# Adafruit_tftcaptouchshield_v2_3.net
KiCad netlist of a schematic drawn in EAGLE
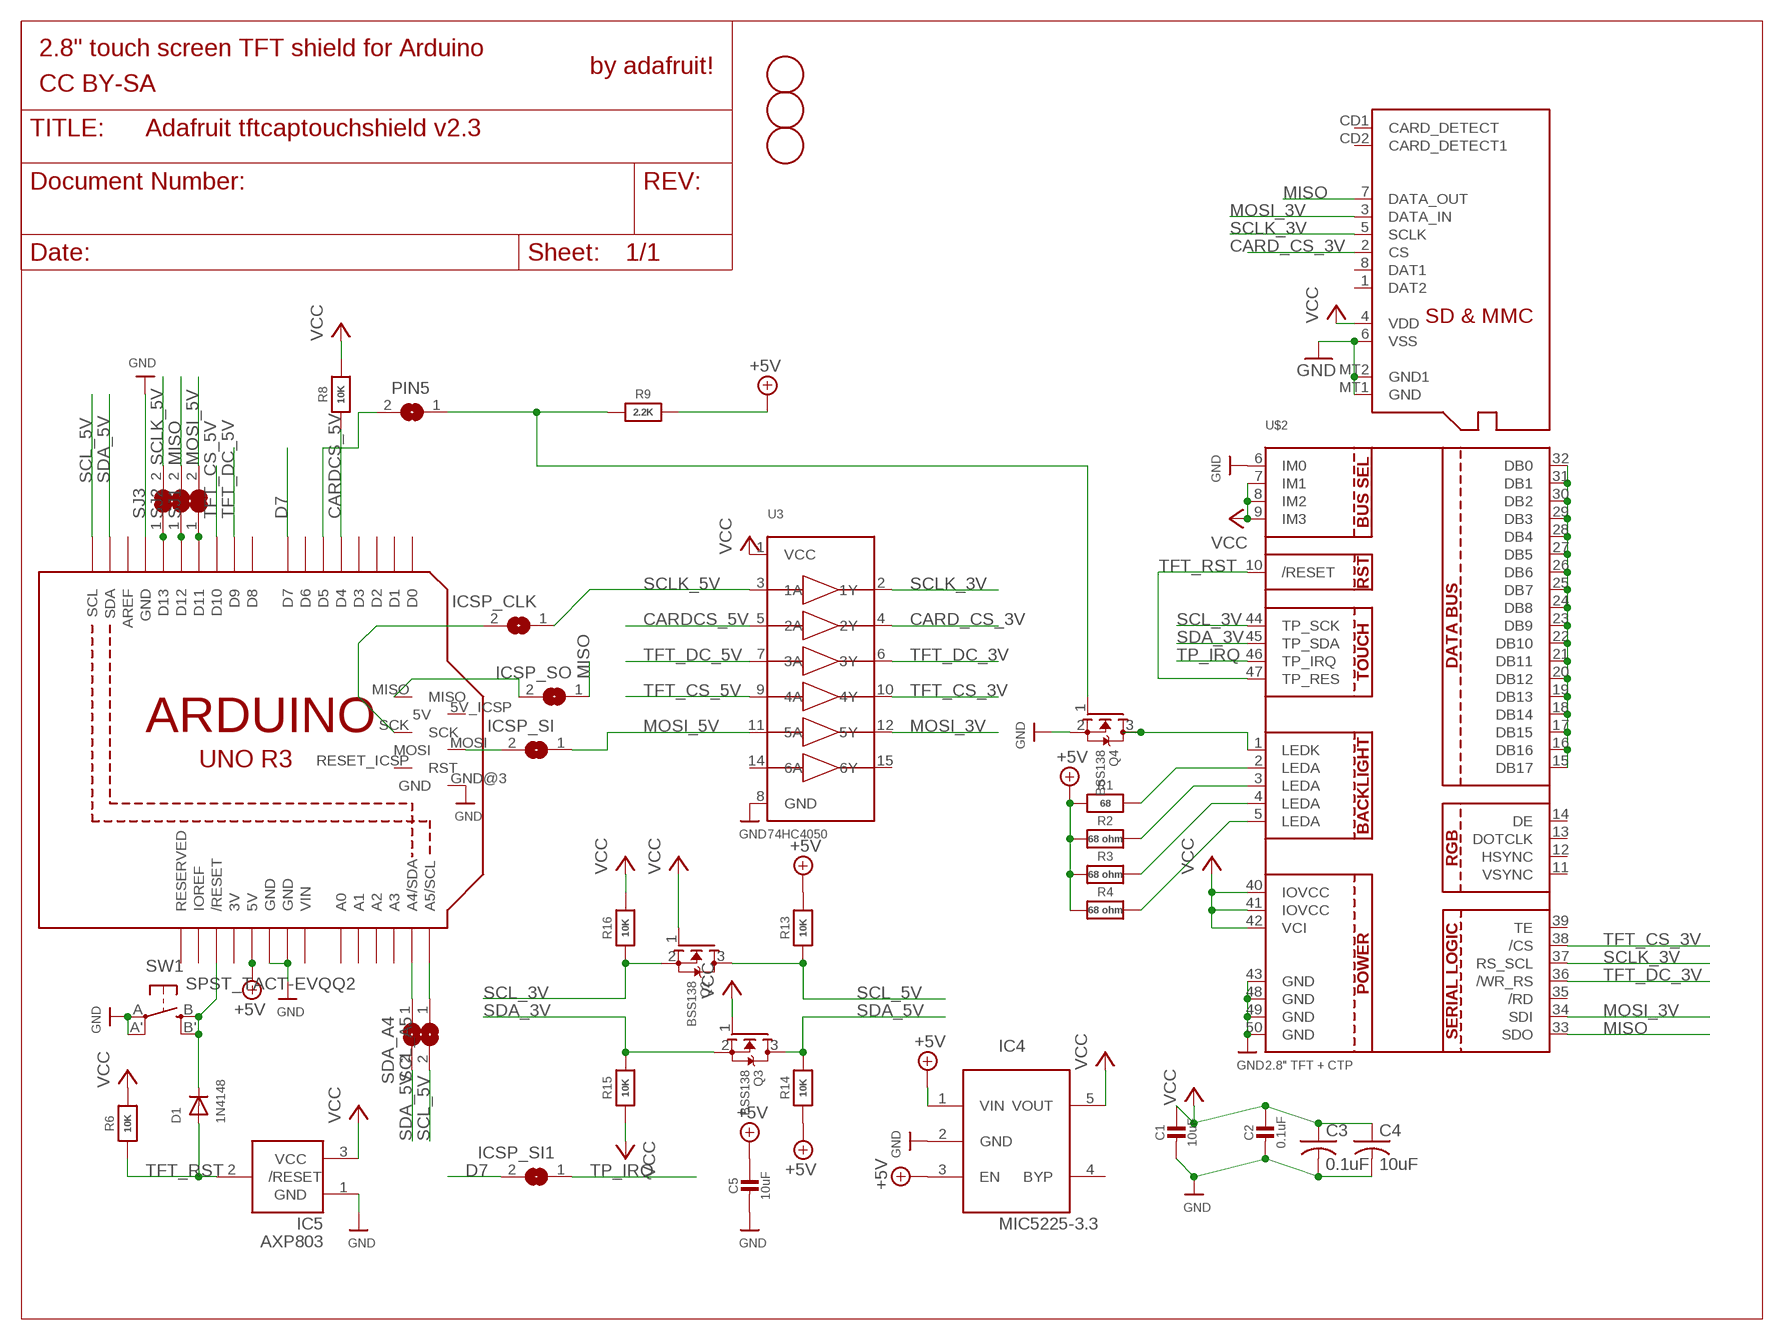
[diagram p0: schematic, sheet 1]

(export (version "E")
  (design (tool "Eeschema 10.0.6"))
  (components
    (comp (ref "C1")
      (value "10uF")
      (footprint "eagle-import:0805-NO")
      (libsource (lib "eagle-import") (part "CAP_CERAMIC0805-NOOUTLINE"))
    )
    (comp (ref "C2")
      (value "0.1uF")
      (footprint "eagle-import:0805-NO")
      (libsource (lib "eagle-import") (part "CAP_CERAMIC0805-NOOUTLINE"))
    )
    (comp (ref "C3")
      (value "0.1uF")
      (footprint "eagle-import:C0805K")
      (libsource (lib "eagle-import") (part "C-USC0805K"))
    )
    (comp (ref "C4")
      (value "10uF")
      (footprint "eagle-import:C0805K")
      (libsource (lib "eagle-import") (part "C-USC0805K"))
    )
    (comp (ref "C5")
      (value "10uF")
      (footprint "eagle-import:0805-NO")
      (libsource (lib "eagle-import") (part "CAP_CERAMIC0805-NOOUTLINE"))
    )
    (comp (ref "D1")
      (value "1N4148")
      (footprint "eagle-import:SOD-323F")
      (libsource (lib "eagle-import") (part "DIODESOD-323F"))
    )
    (comp (ref "IC4")
      (value "MIC5225-3.3")
      (footprint "eagle-import:SOT23-5L")
      (libsource (lib "eagle-import") (part "LP298XS"))
    )
    (comp (ref "IC5")
      (value "AXP803")
      (footprint "eagle-import:SOT23")
      (libsource (lib "eagle-import") (part "AXP083-SAG"))
    )
    (comp (ref "ICSP_CLK")
      (value "SOLDERJUMPERREFLOW_NOPASTE")
      (footprint "eagle-import:SOLDERJUMPER_REFLOW_NOPASTE")
      (libsource (lib "eagle-import") (part "SOLDERJUMPERREFLOW_NOPASTE"))
    )
    (comp (ref "ICSP_SI")
      (value "SOLDERJUMPERREFLOW_NOPASTE")
      (footprint "eagle-import:SOLDERJUMPER_REFLOW_NOPASTE")
      (libsource (lib "eagle-import") (part "SOLDERJUMPERREFLOW_NOPASTE"))
    )
    (comp (ref "ICSP_SI1")
      (value "SOLDERJUMPERREFLOW_NOPASTE")
      (footprint "eagle-import:SOLDERJUMPER_REFLOW_NOPASTE")
      (libsource (lib "eagle-import") (part "SOLDERJUMPERREFLOW_NOPASTE"))
    )
    (comp (ref "ICSP_SO")
      (value "SOLDERJUMPERREFLOW_NOPASTE")
      (footprint "eagle-import:SOLDERJUMPER_REFLOW_NOPASTE")
      (libsource (lib "eagle-import") (part "SOLDERJUMPERREFLOW_NOPASTE"))
    )
    (comp (ref "PIN5")
      (value "SOLDERJUMPERREFLOW_NOPASTE")
      (footprint "eagle-import:SOLDERJUMPER_REFLOW_NOPASTE")
      (libsource (lib "eagle-import") (part "SOLDERJUMPERREFLOW_NOPASTE"))
    )
    (comp (ref "Q2")
      (value "BSS138")
      (footprint "eagle-import:SOT23-WIDE")
      (libsource (lib "eagle-import") (part "MOSFET-NWIDE"))
    )
    (comp (ref "Q3")
      (value "BSS138")
      (footprint "eagle-import:SOT23-WIDE")
      (libsource (lib "eagle-import") (part "MOSFET-NWIDE"))
    )
    (comp (ref "Q4")
      (value "BSS138")
      (footprint "eagle-import:SOT23-WIDE")
      (libsource (lib "eagle-import") (part "MOSFET-NWIDE"))
    )
    (comp (ref "R1")
      (value "68")
      (footprint "eagle-import:0805-NO")
      (libsource (lib "eagle-import") (part "RESISTOR0805_NOOUTLINE"))
    )
    (comp (ref "R2")
      (value "68 ohm")
      (footprint "eagle-import:0805-NO")
      (libsource (lib "eagle-import") (part "RESISTOR0805_NOOUTLINE"))
    )
    (comp (ref "R3")
      (value "68 ohm")
      (footprint "eagle-import:0805-NO")
      (libsource (lib "eagle-import") (part "RESISTOR0805_NOOUTLINE"))
    )
    (comp (ref "R4")
      (value "68 ohm")
      (footprint "eagle-import:0805-NO")
      (libsource (lib "eagle-import") (part "RESISTOR0805_NOOUTLINE"))
    )
    (comp (ref "R6")
      (value "10K")
      (footprint "eagle-import:0805-NO")
      (libsource (lib "eagle-import") (part "RESISTOR0805_NOOUTLINE"))
    )
    (comp (ref "R8")
      (value "10K")
      (footprint "eagle-import:0805-NO")
      (libsource (lib "eagle-import") (part "RESISTOR0805_NOOUTLINE"))
    )
    (comp (ref "R9")
      (value "2.2K")
      (footprint "eagle-import:0805-NO")
      (libsource (lib "eagle-import") (part "RESISTOR0805_NOOUTLINE"))
    )
    (comp (ref "R13")
      (value "10K")
      (footprint "eagle-import:0805-NO")
      (libsource (lib "eagle-import") (part "RESISTOR0805_NOOUTLINE"))
    )
    (comp (ref "R14")
      (value "10K")
      (footprint "eagle-import:0805-NO")
      (libsource (lib "eagle-import") (part "RESISTOR0805_NOOUTLINE"))
    )
    (comp (ref "R15")
      (value "10K")
      (footprint "eagle-import:0805-NO")
      (libsource (lib "eagle-import") (part "RESISTOR0805_NOOUTLINE"))
    )
    (comp (ref "R16")
      (value "10K")
      (footprint "eagle-import:0805-NO")
      (libsource (lib "eagle-import") (part "RESISTOR0805_NOOUTLINE"))
    )
    (comp (ref "SCL_A5")
      (value "SOLDERJUMPERREFLOW_NOPASTE")
      (footprint "eagle-import:SOLDERJUMPER_REFLOW_NOPASTE")
      (libsource (lib "eagle-import") (part "SOLDERJUMPERREFLOW_NOPASTE"))
    )
    (comp (ref "SDA_A4")
      (value "SOLDERJUMPERREFLOW_NOPASTE")
      (footprint "eagle-import:SOLDERJUMPER_REFLOW_NOPASTE")
      (libsource (lib "eagle-import") (part "SOLDERJUMPERREFLOW_NOPASTE"))
    )
    (comp (ref "SJ1")
      (value "SOLDERJUMPER_CLOSED")
      (footprint "eagle-import:SOLDERJUMPER_CLOSEDWIRE")
      (libsource (lib "eagle-import") (part "SOLDERJUMPER_CLOSED"))
    )
    (comp (ref "SJ2")
      (value "SOLDERJUMPER_CLOSED")
      (footprint "eagle-import:SOLDERJUMPER_CLOSEDWIRE")
      (libsource (lib "eagle-import") (part "SOLDERJUMPER_CLOSED"))
    )
    (comp (ref "SJ3")
      (value "SOLDERJUMPER_CLOSED")
      (footprint "eagle-import:SOLDERJUMPER_CLOSEDWIRE")
      (libsource (lib "eagle-import") (part "SOLDERJUMPER_CLOSED"))
    )
    (comp (ref "SW1")
      (value "SPST_TACT-EVQQ2")
      (footprint "eagle-import:EVQ-Q2")
      (libsource (lib "eagle-import") (part "SPST_TACT-EVQQ2"))
    )
    (comp (ref "U$2")
      (value "2.8\" TFT + CTP")
      (footprint "eagle-import:TFT_2.83IN_240X320_50PIN")
      (libsource (lib "eagle-import") (part "DISP_LCD_CTP28_SAMPLE"))
    )
    (comp (ref "U$3")
      (value "MICROSD")
      (footprint "eagle-import:MICROSD")
      (libsource (lib "eagle-import") (part "MICROSD"))
    )
    (comp (ref "U$10")
      (value "FIDUCIAL")
      (footprint "eagle-import:FIDUCIAL_1MM")
      (libsource (lib "eagle-import") (part "FIDUCIAL"))
    )
    (comp (ref "U$11")
      (value "FIDUCIAL")
      (footprint "eagle-import:FIDUCIAL_1MM")
      (libsource (lib "eagle-import") (part "FIDUCIAL"))
    )
    (comp (ref "U$17")
      (value "ARDUINO_R3_ICSPSMT")
      (footprint "eagle-import:ARDUINOR3_ICSP_SMT")
      (libsource (lib "eagle-import") (part "ARDUINO_R3_ICSPSMT"))
    )
    (comp (ref "U$19")
      (value "FIDUCIAL")
      (footprint "eagle-import:FIDUCIAL_1MM")
      (libsource (lib "eagle-import") (part "FIDUCIAL"))
    )
    (comp (ref "U3")
      (value "74HC4050")
      (footprint "eagle-import:SOIC16")
      (libsource (lib "eagle-import") (part "74HC4050D"))
    )
  )
  (nets
    (net (code "1") (name "+5V") (class "Default")
      (node (ref "C5") (pin "1") (pinfunction "1_1") (pintype "passive"))
      (node (ref "IC4") (pin "1") (pinfunction "VIN_1") (pintype "bidirectional"))
      (node (ref "IC4") (pin "3") (pinfunction "EN_3") (pintype "bidirectional"))
      (node (ref "R1") (pin "1") (pinfunction "1_1") (pintype "passive"))
      (node (ref "R13") (pin "2") (pinfunction "2_2") (pintype "passive"))
      (node (ref "R14") (pin "1") (pinfunction "1_1") (pintype "passive"))
      (node (ref "R2") (pin "1") (pinfunction "1_1") (pintype "passive"))
      (node (ref "R3") (pin "1") (pinfunction "1_1") (pintype "passive"))
      (node (ref "R4") (pin "1") (pinfunction "1_1") (pintype "passive"))
      (node (ref "R9") (pin "2") (pinfunction "2_2") (pintype "passive"))
      (node (ref "U$17") (pin "5V") (pinfunction "5V_5V") (pintype "power_in"))
    )
    (net (code "2") (name "/3V") (class "Default")
      (node (ref "U$17") (pin "3V") (pinfunction "3V_3V") (pintype "power_in"))
    )
    (net (code "3") (name "/CARDCS_5V") (class "Default")
      (node (ref "R8") (pin "1") (pinfunction "1_1") (pintype "passive"))
      (node (ref "U$17") (pin "D4") (pinfunction "D4_D4") (pintype "bidirectional"))
      (node (ref "U3") (pin "5") (pinfunction "2A_5") (pintype "bidirectional"))
    )
    (net (code "4") (name "/CARD_CS_3V") (class "Default")
      (node (ref "U$3") (pin "2") (pinfunction "CS_2") (pintype "input"))
      (node (ref "U3") (pin "4") (pinfunction "2Y_4") (pintype "bidirectional"))
    )
    (net (code "5") (name "/D7") (class "Default")
      (node (ref "ICSP_SI1") (pin "2") (pinfunction "2_2") (pintype "passive"))
      (node (ref "U$17") (pin "D7") (pinfunction "D7_D7") (pintype "bidirectional"))
    )
    (net (code "6") (name "/MISO") (class "Default")
      (node (ref "ICSP_SO") (pin "1") (pinfunction "1_1") (pintype "passive"))
      (node (ref "SJ2") (pin "2") (pinfunction "2_2") (pintype "passive"))
      (node (ref "U$2") (pin "33") (pinfunction "SDO_33") (pintype "bidirectional"))
      (node (ref "U$3") (pin "7") (pinfunction "DATA_OUT_7") (pintype "output"))
    )
    (net (code "7") (name "/MOSI_3V") (class "Default")
      (node (ref "U$2") (pin "34") (pinfunction "SDI_34") (pintype "bidirectional"))
      (node (ref "U$3") (pin "3") (pinfunction "DATA_IN_3") (pintype "input"))
      (node (ref "U3") (pin "12") (pinfunction "5Y_12") (pintype "bidirectional"))
    )
    (net (code "8") (name "/MOSI_5V") (class "Default")
      (node (ref "ICSP_SI") (pin "1") (pinfunction "1_1") (pintype "passive"))
      (node (ref "SJ1") (pin "2") (pinfunction "2_2") (pintype "passive"))
      (node (ref "U3") (pin "11") (pinfunction "5A_11") (pintype "bidirectional"))
    )
    (net (code "9") (name "/SCLK_3V") (class "Default")
      (node (ref "U$2") (pin "37") (pinfunction "RS_SCL_37") (pintype "bidirectional"))
      (node (ref "U$3") (pin "5") (pinfunction "SCLK_5") (pintype "input"))
      (node (ref "U3") (pin "2") (pinfunction "1Y_2") (pintype "bidirectional"))
    )
    (net (code "10") (name "/SCLK_5V") (class "Default")
      (node (ref "ICSP_CLK") (pin "1") (pinfunction "1_1") (pintype "passive"))
      (node (ref "SJ3") (pin "2") (pinfunction "2_2") (pintype "passive"))
      (node (ref "U3") (pin "3") (pinfunction "1A_3") (pintype "bidirectional"))
    )
    (net (code "11") (name "/SCL_3V") (class "Default")
      (node (ref "Q2") (pin "2") (pinfunction "S_2") (pintype "bidirectional"))
      (node (ref "R16") (pin "1") (pinfunction "1_1") (pintype "passive"))
      (node (ref "U$2") (pin "44") (pinfunction "TP_SCK_44") (pintype "bidirectional"))
    )
    (net (code "12") (name "/SCL_5V") (class "Default")
      (node (ref "Q2") (pin "3") (pinfunction "D_3") (pintype "bidirectional"))
      (node (ref "R13") (pin "1") (pinfunction "1_1") (pintype "passive"))
      (node (ref "SCL_A5") (pin "2") (pinfunction "2_2") (pintype "passive"))
      (node (ref "U$17") (pin "SCL") (pinfunction "SCL_SCL") (pintype "bidirectional"))
    )
    (net (code "13") (name "/SDA_3V") (class "Default")
      (node (ref "Q3") (pin "2") (pinfunction "S_2") (pintype "bidirectional"))
      (node (ref "R15") (pin "2") (pinfunction "2_2") (pintype "passive"))
      (node (ref "U$2") (pin "45") (pinfunction "TP_SDA_45") (pintype "bidirectional"))
    )
    (net (code "14") (name "/SDA_5V") (class "Default")
      (node (ref "Q3") (pin "3") (pinfunction "D_3") (pintype "bidirectional"))
      (node (ref "R14") (pin "2") (pinfunction "2_2") (pintype "passive"))
      (node (ref "SDA_A4") (pin "2") (pinfunction "2_2") (pintype "passive"))
      (node (ref "U$17") (pin "SDA") (pinfunction "SDA_SDA") (pintype "bidirectional"))
    )
    (net (code "15") (name "/TFT_CS_3V") (class "Default")
      (node (ref "U$2") (pin "38") (pinfunction "/CS_38") (pintype "bidirectional"))
      (node (ref "U3") (pin "10") (pinfunction "4Y_10") (pintype "bidirectional"))
    )
    (net (code "16") (name "/TFT_CS_5V") (class "Default")
      (node (ref "U$17") (pin "D10") (pinfunction "D10_D10") (pintype "bidirectional"))
      (node (ref "U3") (pin "9") (pinfunction "4A_9") (pintype "bidirectional"))
    )
    (net (code "17") (name "/TFT_DC_3V") (class "Default")
      (node (ref "U$2") (pin "36") (pinfunction "/WR_RS_36") (pintype "bidirectional"))
      (node (ref "U3") (pin "6") (pinfunction "3Y_6") (pintype "bidirectional"))
    )
    (net (code "18") (name "/TFT_DC_5V") (class "Default")
      (node (ref "U$17") (pin "D9") (pinfunction "D9_D9") (pintype "bidirectional"))
      (node (ref "U3") (pin "7") (pinfunction "3A_7") (pintype "bidirectional"))
    )
    (net (code "19") (name "/TFT_RST") (class "Default")
      (node (ref "D1") (pin "A") (pinfunction "A_A") (pintype "passive"))
      (node (ref "IC5") (pin "2") (pinfunction "/RESET_2") (pintype "output"))
      (node (ref "R6") (pin "1") (pinfunction "1_1") (pintype "passive"))
      (node (ref "U$2") (pin "10") (pinfunction "/RESET_10") (pintype "bidirectional"))
      (node (ref "U$2") (pin "47") (pinfunction "TP_RES_47") (pintype "bidirectional"))
    )
    (net (code "20") (name "/TP_IRQ") (class "Default")
      (node (ref "ICSP_SI1") (pin "1") (pinfunction "1_1") (pintype "passive"))
      (node (ref "U$2") (pin "46") (pinfunction "TP_IRQ_46") (pintype "bidirectional"))
    )
    (net (code "21") (name "/VIN") (class "Default")
      (node (ref "U$17") (pin "VIN") (pinfunction "VIN_VIN") (pintype "power_in"))
    )
    (net (code "22") (name "GND") (class "Default")
      (node (ref "C1") (pin "2") (pinfunction "2_2") (pintype "passive"))
      (node (ref "C2") (pin "2") (pinfunction "2_2") (pintype "passive"))
      (node (ref "C3") (pin "2") (pinfunction "2_2") (pintype "passive"))
      (node (ref "C4") (pin "2") (pinfunction "2_2") (pintype "passive"))
      (node (ref "C5") (pin "2") (pinfunction "2_2") (pintype "passive"))
      (node (ref "IC4") (pin "2") (pinfunction "GND_2") (pintype "bidirectional"))
      (node (ref "IC5") (pin "1") (pinfunction "GND_1") (pintype "power_in"))
      (node (ref "Q4") (pin "2") (pinfunction "S_2") (pintype "bidirectional"))
      (node (ref "SW1") (pin "A") (pinfunction "P_A") (pintype "passive"))
      (node (ref "SW1") (pin "A'") (pinfunction "P1_A'") (pintype "passive"))
      (node (ref "U$17") (pin "GND") (pinfunction "GND_GND") (pintype "power_in"))
      (node (ref "U$17") (pin "GND@1") (pinfunction "GND_GND@1") (pintype "power_in"))
      (node (ref "U$17") (pin "GND@2") (pinfunction "GND_GND@2") (pintype "power_in"))
      (node (ref "U$17") (pin "GND@3") (pinfunction "GND_GND@3") (pintype "passive"))
      (node (ref "U$2") (pin "43") (pinfunction "GND_43") (pintype "bidirectional"))
      (node (ref "U$2") (pin "48") (pinfunction "GND_48") (pintype "bidirectional"))
      (node (ref "U$2") (pin "49") (pinfunction "GND_49") (pintype "bidirectional"))
      (node (ref "U$2") (pin "50") (pinfunction "GND_50") (pintype "bidirectional"))
      (node (ref "U$2") (pin "6") (pinfunction "IM0_6") (pintype "bidirectional"))
      (node (ref "U$3") (pin "6") (pinfunction "VSS_6") (pintype "power_in"))
      (node (ref "U$3") (pin "MT1") (pinfunction "GND_MT1") (pintype "power_in"))
      (node (ref "U$3") (pin "MT2") (pinfunction "GND1_MT2") (pintype "power_in"))
      (node (ref "U3") (pin "8") (pinfunction "GND_8") (pintype "bidirectional"))
    )
    (net (code "23") (name "Net-(ICSP_CLK-Pad2)") (class "Default")
      (node (ref "ICSP_CLK") (pin "2") (pinfunction "2_2") (pintype "passive"))
      (node (ref "U$17") (pin "SCK") (pinfunction "SCK_SCK") (pintype "passive"))
    )
    (net (code "24") (name "Net-(ICSP_SI-Pad2)") (class "Default")
      (node (ref "ICSP_SI") (pin "2") (pinfunction "2_2") (pintype "passive"))
      (node (ref "U$17") (pin "MOSI") (pinfunction "MOSI_MOSI") (pintype "passive"))
    )
    (net (code "25") (name "Net-(ICSP_SO-Pad2)") (class "Default")
      (node (ref "ICSP_SO") (pin "2") (pinfunction "2_2") (pintype "passive"))
      (node (ref "U$17") (pin "MISO") (pinfunction "MISO_MISO") (pintype "passive"))
    )
    (net (code "26") (name "Net-(PIN5-Pad2)") (class "Default")
      (node (ref "PIN5") (pin "2") (pinfunction "2_2") (pintype "passive"))
      (node (ref "U$17") (pin "D5") (pinfunction "D5_D5") (pintype "bidirectional"))
    )
    (net (code "27") (name "Net-(Q4-D)") (class "Default")
      (node (ref "Q4") (pin "3") (pinfunction "D_3") (pintype "bidirectional"))
      (node (ref "U$2") (pin "1") (pinfunction "LEDK_1") (pintype "bidirectional"))
    )
    (net (code "28") (name "Net-(Q4-G)") (class "Default")
      (node (ref "PIN5") (pin "1") (pinfunction "1_1") (pintype "passive"))
      (node (ref "Q4") (pin "1") (pinfunction "G_1") (pintype "bidirectional"))
      (node (ref "R9") (pin "1") (pinfunction "1_1") (pintype "passive"))
    )
    (net (code "29") (name "Net-(R1-Pad2)") (class "Default")
      (node (ref "R1") (pin "2") (pinfunction "2_2") (pintype "passive"))
      (node (ref "U$2") (pin "2") (pinfunction "LEDA_2") (pintype "bidirectional"))
    )
    (net (code "30") (name "Net-(R2-Pad2)") (class "Default")
      (node (ref "R2") (pin "2") (pinfunction "2_2") (pintype "passive"))
      (node (ref "U$2") (pin "3") (pinfunction "LEDA_3") (pintype "bidirectional"))
    )
    (net (code "31") (name "Net-(R3-Pad2)") (class "Default")
      (node (ref "R3") (pin "2") (pinfunction "2_2") (pintype "passive"))
      (node (ref "U$2") (pin "4") (pinfunction "LEDA_4") (pintype "bidirectional"))
    )
    (net (code "32") (name "Net-(R4-Pad2)") (class "Default")
      (node (ref "R4") (pin "2") (pinfunction "2_2") (pintype "passive"))
      (node (ref "U$2") (pin "5") (pinfunction "LEDA_5") (pintype "bidirectional"))
    )
    (net (code "33") (name "Net-(SJ1-Pad1)") (class "Default")
      (node (ref "SJ1") (pin "1") (pinfunction "1_1") (pintype "passive"))
      (node (ref "U$17") (pin "D11") (pinfunction "D11_D11") (pintype "bidirectional"))
    )
    (net (code "34") (name "Net-(SJ2-Pad1)") (class "Default")
      (node (ref "SJ2") (pin "1") (pinfunction "1_1") (pintype "passive"))
      (node (ref "U$17") (pin "D12") (pinfunction "D12_D12") (pintype "bidirectional"))
    )
    (net (code "35") (name "Net-(SJ3-Pad1)") (class "Default")
      (node (ref "SJ3") (pin "1") (pinfunction "1_1") (pintype "passive"))
      (node (ref "U$17") (pin "D13") (pinfunction "D13_D13") (pintype "bidirectional"))
    )
    (net (code "36") (name "Net-(SW1-S)") (class "Default")
      (node (ref "D1") (pin "C") (pinfunction "C_C") (pintype "passive"))
      (node (ref "SW1") (pin "B") (pinfunction "S_B") (pintype "passive"))
      (node (ref "SW1") (pin "B'") (pinfunction "S1_B'") (pintype "passive"))
      (node (ref "U$17") (pin "RESET") (pinfunction "/RESET_RESET") (pintype "bidirectional"))
    )
    (net (code "37") (name "Net-(U$2-DB0)") (class "Default")
      (node (ref "U$2") (pin "15") (pinfunction "DB17_15") (pintype "bidirectional"))
      (node (ref "U$2") (pin "16") (pinfunction "DB16_16") (pintype "bidirectional"))
      (node (ref "U$2") (pin "17") (pinfunction "DB15_17") (pintype "bidirectional"))
      (node (ref "U$2") (pin "18") (pinfunction "DB14_18") (pintype "bidirectional"))
      (node (ref "U$2") (pin "19") (pinfunction "DB13_19") (pintype "bidirectional"))
      (node (ref "U$2") (pin "20") (pinfunction "DB12_20") (pintype "bidirectional"))
      (node (ref "U$2") (pin "21") (pinfunction "DB11_21") (pintype "bidirectional"))
      (node (ref "U$2") (pin "22") (pinfunction "DB10_22") (pintype "bidirectional"))
      (node (ref "U$2") (pin "23") (pinfunction "DB9_23") (pintype "bidirectional"))
      (node (ref "U$2") (pin "24") (pinfunction "DB8_24") (pintype "bidirectional"))
      (node (ref "U$2") (pin "25") (pinfunction "DB7_25") (pintype "bidirectional"))
      (node (ref "U$2") (pin "26") (pinfunction "DB6_26") (pintype "bidirectional"))
      (node (ref "U$2") (pin "27") (pinfunction "DB5_27") (pintype "bidirectional"))
      (node (ref "U$2") (pin "28") (pinfunction "DB4_28") (pintype "bidirectional"))
      (node (ref "U$2") (pin "29") (pinfunction "DB3_29") (pintype "bidirectional"))
      (node (ref "U$2") (pin "30") (pinfunction "DB2_30") (pintype "bidirectional"))
      (node (ref "U$2") (pin "31") (pinfunction "DB1_31") (pintype "bidirectional"))
      (node (ref "U$2") (pin "32") (pinfunction "DB0_32") (pintype "bidirectional"))
    )
    (net (code "38") (name "Net-(U$17-A4{slash}SDA)") (class "Default")
      (node (ref "SDA_A4") (pin "1") (pinfunction "1_1") (pintype "passive"))
      (node (ref "U$17") (pin "A4") (pinfunction "A4/SDA_A4") (pintype "bidirectional"))
    )
    (net (code "39") (name "Net-(U$17-A5{slash}SCL)") (class "Default")
      (node (ref "SCL_A5") (pin "1") (pinfunction "1_1") (pintype "passive"))
      (node (ref "U$17") (pin "A5") (pinfunction "A5/SCL_A5") (pintype "bidirectional"))
    )
    (net (code "40") (name "VCC") (class "Default")
      (node (ref "C1") (pin "1") (pinfunction "1_1") (pintype "passive"))
      (node (ref "C2") (pin "1") (pinfunction "1_1") (pintype "passive"))
      (node (ref "C3") (pin "1") (pinfunction "1_1") (pintype "passive"))
      (node (ref "C4") (pin "1") (pinfunction "1_1") (pintype "passive"))
      (node (ref "IC4") (pin "5") (pinfunction "VOUT_5") (pintype "bidirectional"))
      (node (ref "IC5") (pin "3") (pinfunction "VCC_3") (pintype "power_in"))
      (node (ref "Q2") (pin "1") (pinfunction "G_1") (pintype "bidirectional"))
      (node (ref "Q3") (pin "1") (pinfunction "G_1") (pintype "bidirectional"))
      (node (ref "R15") (pin "1") (pinfunction "1_1") (pintype "passive"))
      (node (ref "R16") (pin "2") (pinfunction "2_2") (pintype "passive"))
      (node (ref "R6") (pin "2") (pinfunction "2_2") (pintype "passive"))
      (node (ref "R8") (pin "2") (pinfunction "2_2") (pintype "passive"))
      (node (ref "U$2") (pin "40") (pinfunction "IOVCC_40") (pintype "bidirectional"))
      (node (ref "U$2") (pin "41") (pinfunction "IOVCC_41") (pintype "bidirectional"))
      (node (ref "U$2") (pin "42") (pinfunction "VCI_42") (pintype "bidirectional"))
      (node (ref "U$2") (pin "7") (pinfunction "IM1_7") (pintype "bidirectional"))
      (node (ref "U$2") (pin "8") (pinfunction "IM2_8") (pintype "bidirectional"))
      (node (ref "U$2") (pin "9") (pinfunction "IM3_9") (pintype "bidirectional"))
      (node (ref "U$3") (pin "4") (pinfunction "VDD_4") (pintype "power_in"))
      (node (ref "U3") (pin "1") (pinfunction "VCC_1") (pintype "bidirectional"))
    )
    (net (code "41") (name "unconnected-(IC4-BYP-Pad4)") (class "Default")
      (node (ref "IC4") (pin "4") (pinfunction "BYP_4") (pintype "bidirectional"))
    )
    (net (code "42") (name "unconnected-(U$2-DE-Pad14)") (class "Default")
      (node (ref "U$2") (pin "14") (pinfunction "DE_14") (pintype "bidirectional"))
    )
    (net (code "43") (name "unconnected-(U$2-DOTCLK-Pad13)") (class "Default")
      (node (ref "U$2") (pin "13") (pinfunction "DOTCLK_13") (pintype "bidirectional"))
    )
    (net (code "44") (name "unconnected-(U$2-HSYNC-Pad12)") (class "Default")
      (node (ref "U$2") (pin "12") (pinfunction "HSYNC_12") (pintype "bidirectional"))
    )
    (net (code "45") (name "unconnected-(U$2-TE-Pad39)") (class "Default")
      (node (ref "U$2") (pin "39") (pinfunction "TE_39") (pintype "bidirectional"))
    )
    (net (code "46") (name "unconnected-(U$2-VSYNC-Pad11)") (class "Default")
      (node (ref "U$2") (pin "11") (pinfunction "VSYNC_11") (pintype "bidirectional"))
    )
    (net (code "47") (name "unconnected-(U$2-{slash}RD-Pad35)") (class "Default")
      (node (ref "U$2") (pin "35") (pinfunction "/RD_35") (pintype "bidirectional"))
    )
    (net (code "48") (name "unconnected-(U$3-CARD_DETECT-PadCD1)") (class "Default")
      (node (ref "U$3") (pin "CD1") (pinfunction "CARD_DETECT_CD1") (pintype "passive"))
    )
    (net (code "49") (name "unconnected-(U$3-CARD_DETECT1-PadCD2)") (class "Default")
      (node (ref "U$3") (pin "CD2") (pinfunction "CARD_DETECT1_CD2") (pintype "passive"))
    )
    (net (code "50") (name "unconnected-(U$3-DAT1-Pad8)") (class "Default")
      (node (ref "U$3") (pin "8") (pinfunction "DAT1_8") (pintype "bidirectional"))
    )
    (net (code "51") (name "unconnected-(U$3-DAT2-Pad1)") (class "Default")
      (node (ref "U$3") (pin "1") (pinfunction "DAT2_1") (pintype "bidirectional"))
    )
    (net (code "52") (name "unconnected-(U$17-5V-Pad5V_ICSP)") (class "Default")
      (node (ref "U$17") (pin "5V_ICSP") (pinfunction "5V_5V_ICSP") (pintype "passive"))
    )
    (net (code "53") (name "unconnected-(U$17-PadA0)") (class "Default")
      (node (ref "U$17") (pin "A0") (pinfunction "A0_A0") (pintype "bidirectional"))
    )
    (net (code "54") (name "unconnected-(U$17-PadA1)") (class "Default")
      (node (ref "U$17") (pin "A1") (pinfunction "A1_A1") (pintype "bidirectional"))
    )
    (net (code "55") (name "unconnected-(U$17-PadA2)") (class "Default")
      (node (ref "U$17") (pin "A2") (pinfunction "A2_A2") (pintype "bidirectional"))
    )
    (net (code "56") (name "unconnected-(U$17-PadA3)") (class "Default")
      (node (ref "U$17") (pin "A3") (pinfunction "A3_A3") (pintype "bidirectional"))
    )
    (net (code "57") (name "unconnected-(U$17-PadAREF)") (class "Default")
      (node (ref "U$17") (pin "AREF") (pinfunction "AREF_AREF") (pintype "bidirectional"))
    )
    (net (code "58") (name "unconnected-(U$17-PadD0)") (class "Default")
      (node (ref "U$17") (pin "D0") (pinfunction "D0_D0") (pintype "bidirectional"))
    )
    (net (code "59") (name "unconnected-(U$17-PadD1)") (class "Default")
      (node (ref "U$17") (pin "D1") (pinfunction "D1_D1") (pintype "bidirectional"))
    )
    (net (code "60") (name "unconnected-(U$17-PadD2)") (class "Default")
      (node (ref "U$17") (pin "D2") (pinfunction "D2_D2") (pintype "bidirectional"))
    )
    (net (code "61") (name "unconnected-(U$17-PadD3)") (class "Default")
      (node (ref "U$17") (pin "D3") (pinfunction "D3_D3") (pintype "bidirectional"))
    )
    (net (code "62") (name "unconnected-(U$17-PadD6)") (class "Default")
      (node (ref "U$17") (pin "D6") (pinfunction "D6_D6") (pintype "bidirectional"))
    )
    (net (code "63") (name "unconnected-(U$17-PadD8)") (class "Default")
      (node (ref "U$17") (pin "D8") (pinfunction "D8_D8") (pintype "bidirectional"))
    )
    (net (code "64") (name "unconnected-(U$17-PadIOREF)") (class "Default")
      (node (ref "U$17") (pin "IOREF") (pinfunction "IOREF_IOREF") (pintype "output"))
    )
    (net (code "65") (name "unconnected-(U$17-PadRESERVED)") (class "Default")
      (node (ref "U$17") (pin "RESERVED") (pinfunction "RESERVED_RESERVED") (pintype "no_connect"))
    )
    (net (code "66") (name "unconnected-(U$17-RST-PadRESET_ICSP)") (class "Default")
      (node (ref "U$17") (pin "RESET_ICSP") (pinfunction "RST_RESET_ICSP") (pintype "passive"))
    )
    (net (code "67") (name "unconnected-(U3-6A-Pad14)") (class "Default")
      (node (ref "U3") (pin "14") (pinfunction "6A_14") (pintype "bidirectional"))
    )
    (net (code "68") (name "unconnected-(U3-6Y-Pad15)") (class "Default")
      (node (ref "U3") (pin "15") (pinfunction "6Y_15") (pintype "bidirectional"))
    )
  )
)
